# MCU.net
KiCad netlist of a schematic drawn in Altium Designer
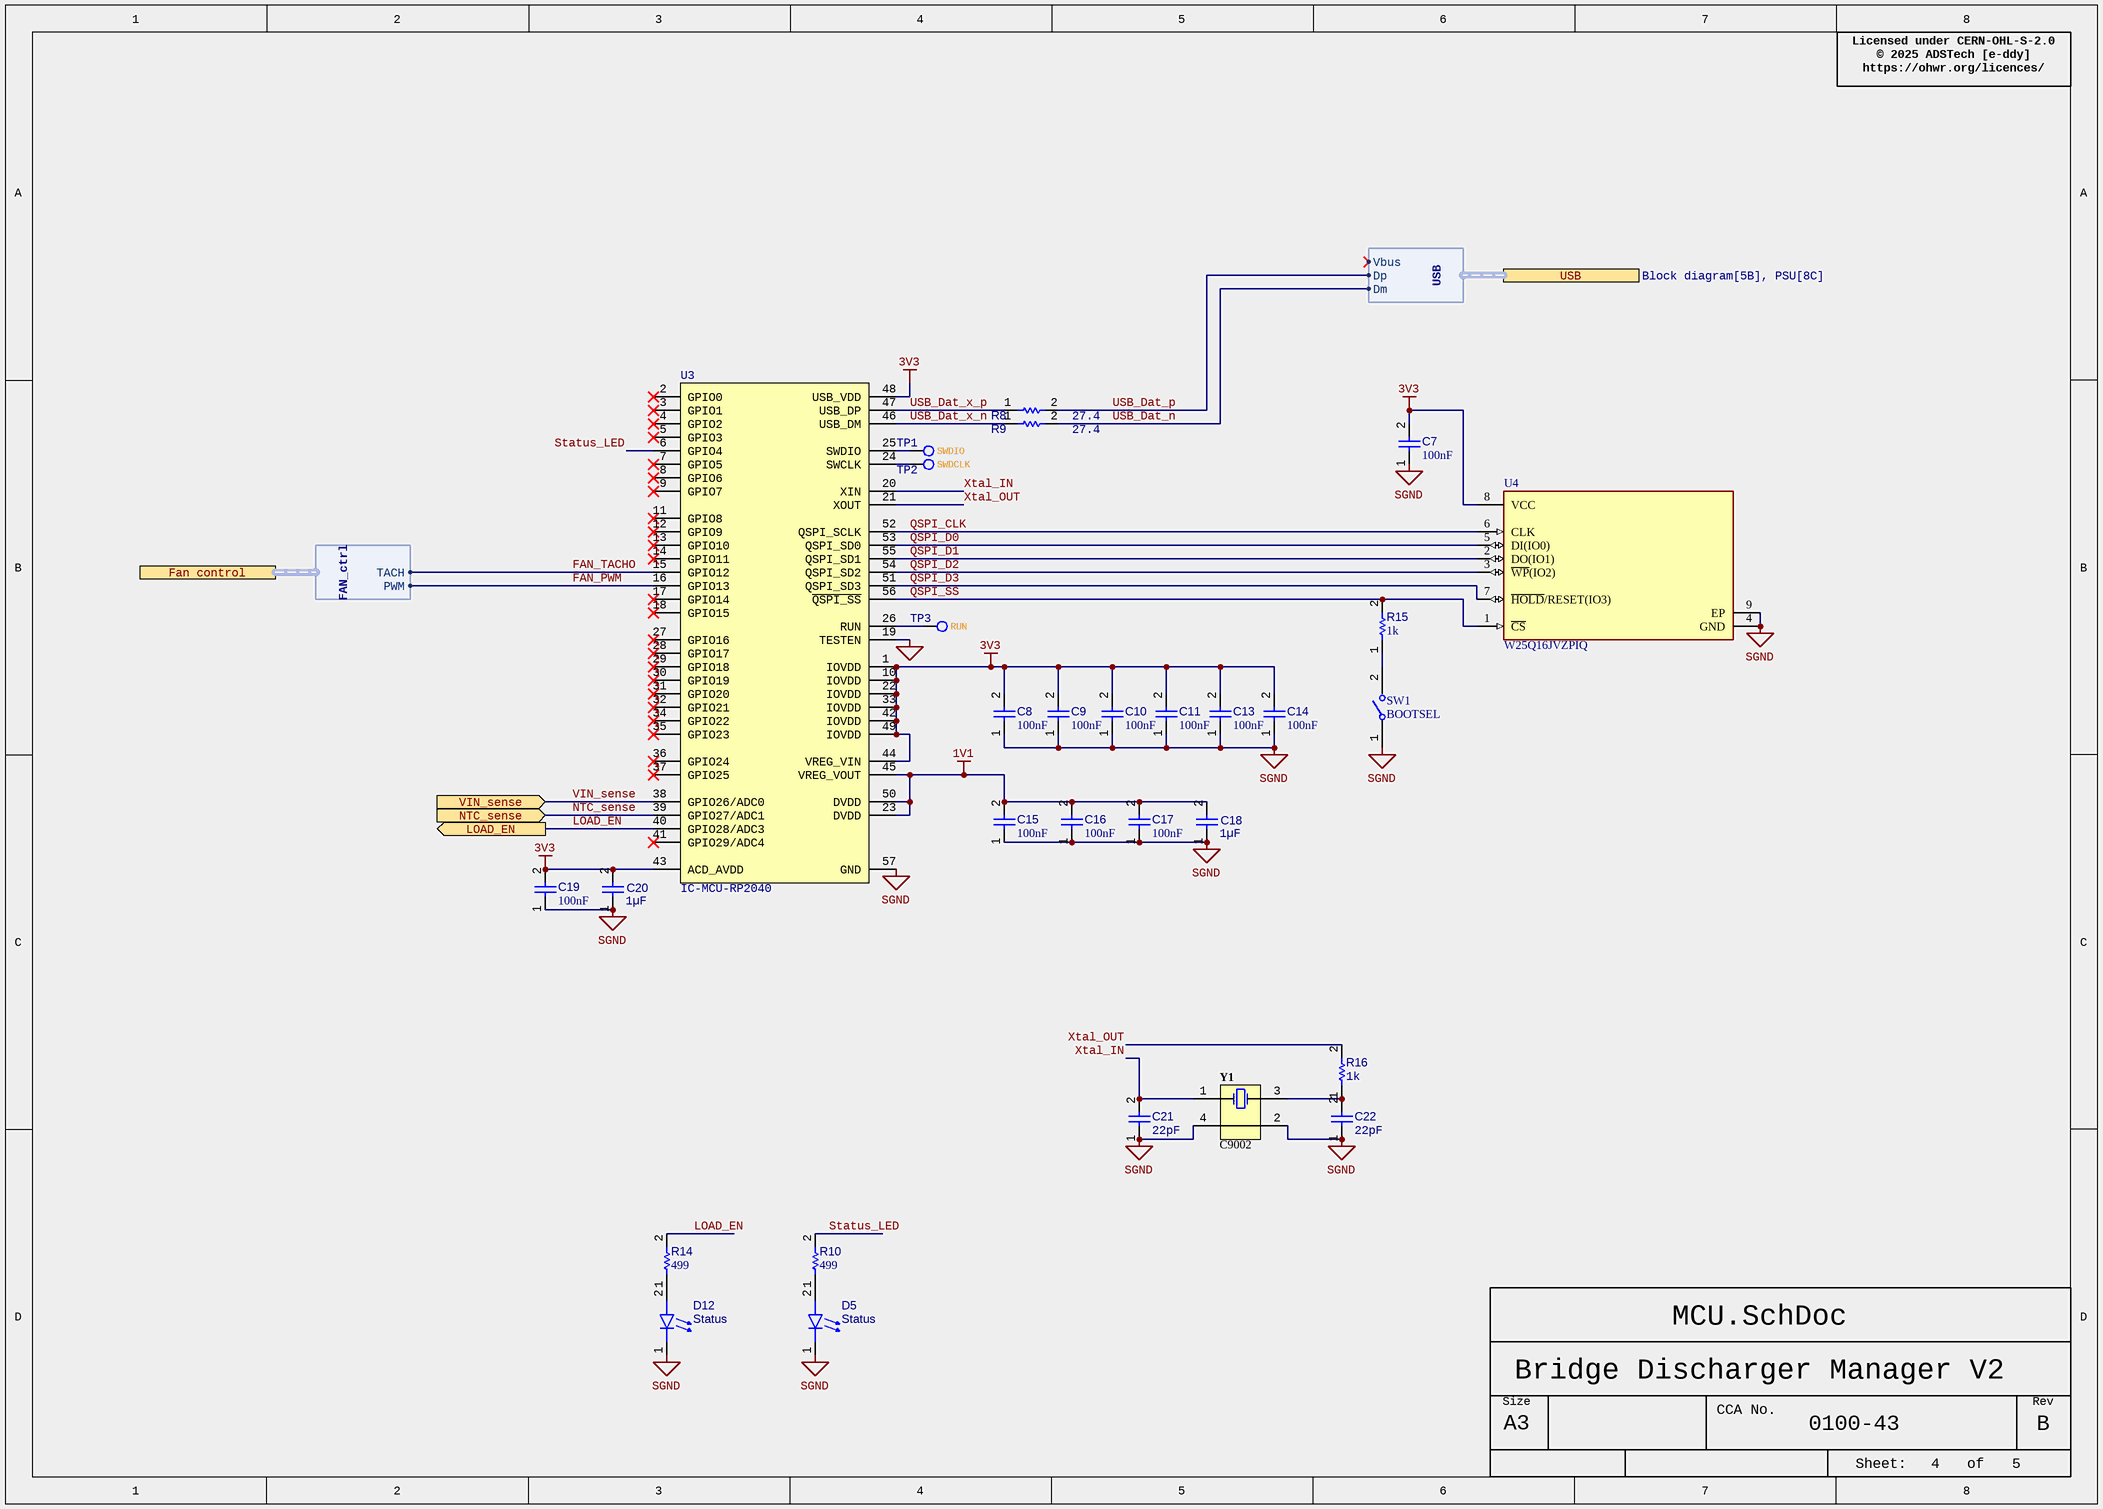
[diagram p0: MCU.SchDoc]

(export (version "E")
  (design (tool "Eeschema 10.0.6"))
  (components
    (comp (ref "C7")
      (value "100nF")
      (footprint "CAP_0402-IPC_B")
      (description "Multilayer Ceramic Capacitor, 0.1 uF, 50 V, ± 10%, X7R, 0402 [1005 Metric]")
      (fields (field (name "TOLERANCE") "10%") (field (name "Comment") "C-0402-CER-X7R-100nF-10%-50V"))
      (libsource (lib "FIME Lille") (part "CAP-NP-2"))
    )
    (comp (ref "C8")
      (value "100nF")
      (footprint "CAP_0402-IPC_B")
      (description "Multilayer Ceramic Capacitor, 0.1 uF, 50 V, ± 10%, X7R, 0402 [1005 Metric]")
      (fields (field (name "TOLERANCE") "10%") (field (name "Comment") "C-0402-CER-X7R-100nF-10%-50V"))
      (libsource (lib "FIME Lille") (part "CAP-NP-2"))
    )
    (comp (ref "C9")
      (value "100nF")
      (footprint "CAP_0402-IPC_B")
      (description "Multilayer Ceramic Capacitor, 0.1 uF, 50 V, ± 10%, X7R, 0402 [1005 Metric]")
      (fields (field (name "TOLERANCE") "10%") (field (name "Comment") "C-0402-CER-X7R-100nF-10%-50V"))
      (libsource (lib "FIME Lille") (part "CAP-NP-2"))
    )
    (comp (ref "C10")
      (value "100nF")
      (footprint "CAP_0402-IPC_B")
      (description "Multilayer Ceramic Capacitor, 0.1 uF, 50 V, ± 10%, X7R, 0402 [1005 Metric]")
      (fields (field (name "TOLERANCE") "10%") (field (name "Comment") "C-0402-CER-X7R-100nF-10%-50V"))
      (libsource (lib "FIME Lille") (part "CAP-NP-2"))
    )
    (comp (ref "C11")
      (value "100nF")
      (footprint "CAP_0402-IPC_B")
      (description "Multilayer Ceramic Capacitor, 0.1 uF, 50 V, ± 10%, X7R, 0402 [1005 Metric]")
      (fields (field (name "TOLERANCE") "10%") (field (name "Comment") "C-0402-CER-X7R-100nF-10%-50V"))
      (libsource (lib "FIME Lille") (part "CAP-NP-2"))
    )
    (comp (ref "C13")
      (value "100nF")
      (footprint "CAP_0402-IPC_B")
      (description "Multilayer Ceramic Capacitor, 0.1 uF, 50 V, ± 10%, X7R, 0402 [1005 Metric]")
      (fields (field (name "TOLERANCE") "10%") (field (name "Comment") "C-0402-CER-X7R-100nF-10%-50V"))
      (libsource (lib "FIME Lille") (part "CAP-NP-2"))
    )
    (comp (ref "C14")
      (value "100nF")
      (footprint "CAP_0402-IPC_B")
      (description "Multilayer Ceramic Capacitor, 0.1 uF, 50 V, ± 10%, X7R, 0402 [1005 Metric]")
      (fields (field (name "TOLERANCE") "10%") (field (name "Comment") "C-0402-CER-X7R-100nF-10%-50V"))
      (libsource (lib "FIME Lille") (part "CAP-NP-2"))
    )
    (comp (ref "C15")
      (value "100nF")
      (footprint "CAP_0402-IPC_B")
      (description "Multilayer Ceramic Capacitor, 0.1 uF, 50 V, ± 10%, X7R, 0402 [1005 Metric]")
      (fields (field (name "TOLERANCE") "10%") (field (name "Comment") "C-0402-CER-X7R-100nF-10%-50V"))
      (libsource (lib "FIME Lille") (part "CAP-NP-2"))
    )
    (comp (ref "C16")
      (value "100nF")
      (footprint "CAP_0402-IPC_B")
      (description "Multilayer Ceramic Capacitor, 0.1 uF, 50 V, ± 10%, X7R, 0402 [1005 Metric]")
      (fields (field (name "TOLERANCE") "10%") (field (name "Comment") "C-0402-CER-X7R-100nF-10%-50V"))
      (libsource (lib "FIME Lille") (part "CAP-NP-2"))
    )
    (comp (ref "C17")
      (value "100nF")
      (footprint "CAP_0402-IPC_B")
      (description "Multilayer Ceramic Capacitor, 0.1 uF, 50 V, ± 10%, X7R, 0402 [1005 Metric]")
      (fields (field (name "TOLERANCE") "10%") (field (name "Comment") "C-0402-CER-X7R-100nF-10%-50V"))
      (libsource (lib "FIME Lille") (part "CAP-NP-2"))
    )
    (comp (ref "C18")
      (value "1µF")
      (footprint "CAP_0402-IPC_B")
      (fields (field (name "Comment") "C-0402-CER-X5R-1µF-10%-25V"))
      (libsource (lib "FIME Lille") (part "CAP-NP-2"))
    )
    (comp (ref "C19")
      (value "100nF")
      (footprint "CAP_0402-IPC_B")
      (description "Multilayer Ceramic Capacitor, 0.1 uF, 50 V, ± 10%, X7R, 0402 [1005 Metric]")
      (fields (field (name "TOLERANCE") "10%") (field (name "Comment") "C-0402-CER-X7R-100nF-10%-50V"))
      (libsource (lib "FIME Lille") (part "CAP-NP-2"))
    )
    (comp (ref "C20")
      (value "1µF")
      (footprint "CAP_0402-IPC_B")
      (fields (field (name "Comment") "C-0402-CER-X5R-1µF-10%-25V"))
      (libsource (lib "FIME Lille") (part "CAP-NP-2"))
    )
    (comp (ref "C21")
      (value "22pF")
      (footprint "CAP_0402-IPC_B")
      (description "Multilayer Ceramic Capacitors MLCC - SMD/SMT 50V 22pF C0G 0402 +/-1%")
      (fields (field (name "TOLERANCE") "1%") (field (name "Comment") "C-0402-C0G-22pF-50V-1%"))
      (libsource (lib "FIME Lille") (part "CAP-NP-2"))
    )
    (comp (ref "C22")
      (value "22pF")
      (footprint "CAP_0402-IPC_B")
      (description "Multilayer Ceramic Capacitors MLCC - SMD/SMT 50V 22pF C0G 0402 +/-1%")
      (fields (field (name "TOLERANCE") "1%") (field (name "Comment") "C-0402-C0G-22pF-50V-1%"))
      (libsource (lib "FIME Lille") (part "CAP-NP-2"))
    )
    (comp (ref "D5")
      (value "Status")
      (footprint "DIAL-0603-2_V")
      (description "Red 633nm 0603 LED")
      (libsource (lib "FIME Lille") (part "DIODE-LED-2"))
    )
    (comp (ref "D12")
      (value "Status")
      (footprint "DIAL-0603-2_V")
      (description "Red 633nm 0603 LED")
      (libsource (lib "FIME Lille") (part "DIODE-LED-2"))
    )
    (comp (ref "R8")
      (value "27.4")
      (footprint "RES-0402-IPC_B")
      (description "0402 27.4 Ω 1% 100ppm 0.063W Resistor")
      (fields (field (name "MPN") "CRCW040227R4FKED") (field (name "TOLERANCE") "1%"))
      (libsource (lib "FIME Lille") (part "RES-2"))
    )
    (comp (ref "R9")
      (value "27.4")
      (footprint "RES-0402-IPC_B")
      (description "0402 27.4 Ω 1% 100ppm 0.063W Resistor")
      (fields (field (name "MPN") "CRCW040227R4FKED") (field (name "TOLERANCE") "1%"))
      (libsource (lib "FIME Lille") (part "RES-2"))
    )
    (comp (ref "R10")
      (value "499")
      (footprint "RES-0402-IPC_B")
      (description "0402 499.0 Ω 1% 100ppm 0.063W Resistor")
      (fields (field (name "TOLERANCE") "1%") (field (name "MPN") "CRCW0402499RFKED"))
      (libsource (lib "FIME Lille") (part "RES-2"))
    )
    (comp (ref "R14")
      (value "499")
      (footprint "RES-0402-IPC_B")
      (description "0402 499.0 Ω 1% 100ppm 0.063W Resistor")
      (fields (field (name "TOLERANCE") "1%") (field (name "MPN") "CRCW0402499RFKED"))
      (libsource (lib "FIME Lille") (part "RES-2"))
    )
    (comp (ref "R15")
      (value "1k")
      (footprint "RES-0402-IPC_B")
      (description "0402 1000.0 Ω 1% 100ppm 0.063W Resistor")
      (fields (field (name "TOLERANCE") "1%") (field (name "MPN") "CRCW04021K00FKED"))
      (libsource (lib "FIME Lille") (part "RES-2"))
    )
    (comp (ref "R16")
      (value "1k")
      (footprint "RES-0402-IPC_B")
      (description "0402 1000.0 Ω 1% 100ppm 0.063W Resistor")
      (fields (field (name "MPN") "CRCW04021K00FKED") (field (name "POWER") "63mW"))
      (libsource (lib "FIME Lille") (part "RES-2"))
    )
    (comp (ref "SW1")
      (value "BOOTSEL")
      (footprint "FP-B3U-1000P-MFG")
      (libsource (lib "FIME Lille") (part "ae622034201233ca1abcedc05908f33"))
    )
    (comp (ref "TP1")
      (value "TP-DIRECT-1.2mm")
      (footprint "1.2mm test point - direct connect")
      (description "1.2mm standard round test point with direct connect")
      (fields (field (name "NAME") "SWDIO"))
      (libsource (lib "FIME Lille") (part "Test point"))
    )
    (comp (ref "TP2")
      (value "TP-DIRECT-1.2mm")
      (footprint "1.2mm test point - direct connect")
      (description "1.2mm standard round test point with direct connect")
      (fields (field (name "NAME") "SWDCLK"))
      (libsource (lib "FIME Lille") (part "Test point"))
    )
    (comp (ref "TP3")
      (value "TP-DIRECT-1.2mm")
      (footprint "1.2mm test point - direct connect")
      (description "1.2mm standard round test point with direct connect")
      (fields (field (name "NAME") "RUN"))
      (libsource (lib "FIME Lille") (part "Test point"))
    )
    (comp (ref "U3")
      (value "IC-MCU-RP2040")
      (footprint "QFN40P700X700X90_HS-57N")
      (description "264KB 30 133MHZ LQFN-56(7X7) Microcontrollers (mcu/mpu/soc) Rohs")
      (libsource (lib "FIME Lille") (part "IC-MCU-RP2040-Symbol-1"))
    )
    (comp (ref "U4")
      (value "W25Q16JVZPIQ")
      (footprint "FP-ZP-IPC_B")
      (description "IC FLASH 16MBIT SPI/QUAD 8WSON")
      (libsource (lib "Altium Content Vault") (part "4cb77c13ae9adfb05a25f85e82aeb43"))
    )
    (comp (ref "Y1")
      (value "C9002")
      (footprint "FP-ABM8-MFG")
      (description "Crystal 12MHz ±20ppm (Tol) ±50ppm (Stability) 18pF FUND 120Ohm 4-Pin Ultra Mini-CSMD T/R")
      (fields (field (name "TOLERANCE") "20ppm"))
      (libsource (lib "FIME Lille") (part "Copy of XTAL-2"))
    )
  )
  (nets
    (net (code "3") (name "/FAN_PWM") (class "Default")
      (node (ref "U3") (pin "16") (pinfunction "GPIO13_16") (pintype "passive"))
    )
    (net (code "4") (name "/FAN_TACHO") (class "Default")
      (node (ref "U3") (pin "15") (pinfunction "GPIO12_15") (pintype "passive"))
    )
    (net (code "5") (name "/LOAD_EN") (class "Default")
      (node (ref "R14") (pin "2") (pinfunction "2_2") (pintype "passive"))
      (node (ref "U3") (pin "40") (pinfunction "GPIO28/ADC3_40") (pintype "passive"))
    )
    (net (code "6") (name "/NTC_sense") (class "Default")
      (node (ref "U3") (pin "39") (pinfunction "GPIO27/ADC1_39") (pintype "passive"))
    )
    (net (code "7") (name "/QSPI_CLK") (class "Default")
      (node (ref "U3") (pin "52") (pinfunction "QSPI_SCLK_52") (pintype "passive"))
      (node (ref "U4") (pin "6") (pinfunction "CLK_6") (pintype "input"))
    )
    (net (code "8") (name "/QSPI_D0") (class "Default")
      (node (ref "U3") (pin "53") (pinfunction "QSPI_SD0_53") (pintype "passive"))
      (node (ref "U4") (pin "5") (pinfunction "DI(IO0)_5") (pintype "bidirectional"))
    )
    (net (code "9") (name "/QSPI_D1") (class "Default")
      (node (ref "U3") (pin "55") (pinfunction "QSPI_SD1_55") (pintype "passive"))
      (node (ref "U4") (pin "2") (pinfunction "DO(IO1)_2") (pintype "bidirectional"))
    )
    (net (code "10") (name "/QSPI_D2") (class "Default")
      (node (ref "U3") (pin "54") (pinfunction "QSPI_SD2_54") (pintype "passive"))
      (node (ref "U4") (pin "3") (pinfunction "~{WP}(IO2)_3") (pintype "bidirectional"))
    )
    (net (code "11") (name "/QSPI_D3") (class "Default")
      (node (ref "U3") (pin "51") (pinfunction "QSPI_SD3_51") (pintype "passive"))
      (node (ref "U4") (pin "7") (pinfunction "~{HOLD}/RESET(IO3)_7") (pintype "bidirectional"))
    )
    (net (code "12") (name "/QSPI_SS") (class "Default")
      (node (ref "R15") (pin "2") (pinfunction "2_2") (pintype "passive"))
      (node (ref "U3") (pin "56") (pinfunction "QSPI_SS_56") (pintype "passive"))
      (node (ref "U4") (pin "1") (pinfunction "~{CS}_1") (pintype "input"))
    )
    (net (code "13") (name "/Status_LED") (class "Default")
      (node (ref "R10") (pin "2") (pinfunction "2_2") (pintype "passive"))
      (node (ref "U3") (pin "6") (pinfunction "GPIO4_6") (pintype "passive"))
    )
    (net (code "14") (name "/USB_Dat_n") (class "Default")
      (node (ref "R9") (pin "2") (pinfunction "2_2") (pintype "passive"))
    )
    (net (code "15") (name "/USB_Dat_p") (class "Default")
      (node (ref "R8") (pin "2") (pinfunction "2_2") (pintype "passive"))
    )
    (net (code "16") (name "/USB_Dat_x_n") (class "Default")
      (node (ref "R9") (pin "1") (pinfunction "1_1") (pintype "passive"))
      (node (ref "U3") (pin "46") (pinfunction "USB_DM_46") (pintype "passive"))
    )
    (net (code "17") (name "/USB_Dat_x_p") (class "Default")
      (node (ref "R8") (pin "1") (pinfunction "1_1") (pintype "passive"))
      (node (ref "U3") (pin "47") (pinfunction "USB_DP_47") (pintype "passive"))
    )
    (net (code "18") (name "/VIN_sense") (class "Default")
      (node (ref "U3") (pin "38") (pinfunction "GPIO26/ADC0_38") (pintype "passive"))
    )
    (net (code "19") (name "/Xtal_IN") (class "Default")
      (node (ref "C21") (pin "2") (pinfunction "2_2") (pintype "passive"))
      (node (ref "U3") (pin "20") (pinfunction "XIN_20") (pintype "passive"))
      (node (ref "Y1") (pin "1") (pinfunction "1_1") (pintype "passive"))
    )
    (net (code "20") (name "/Xtal_OUT") (class "Default")
      (node (ref "R16") (pin "2") (pinfunction "2_2") (pintype "passive"))
      (node (ref "U3") (pin "21") (pinfunction "XOUT_21") (pintype "passive"))
    )
    (net (code "23") (name "1V1") (class "Default")
      (node (ref "C15") (pin "2") (pinfunction "2_2") (pintype "passive"))
      (node (ref "C16") (pin "2") (pinfunction "2_2") (pintype "passive"))
      (node (ref "C17") (pin "2") (pinfunction "2_2") (pintype "passive"))
      (node (ref "C18") (pin "2") (pinfunction "2_2") (pintype "passive"))
      (node (ref "U3") (pin "23") (pinfunction "DVDD_23") (pintype "passive"))
      (node (ref "U3") (pin "45") (pinfunction "VREG_VOUT_45") (pintype "passive"))
      (node (ref "U3") (pin "50") (pinfunction "DVDD_50") (pintype "passive"))
    )
    (net (code "24") (name "3V3") (class "Default")
      (node (ref "C10") (pin "2") (pinfunction "2_2") (pintype "passive"))
      (node (ref "C11") (pin "2") (pinfunction "2_2") (pintype "passive"))
      (node (ref "C13") (pin "2") (pinfunction "2_2") (pintype "passive"))
      (node (ref "C14") (pin "2") (pinfunction "2_2") (pintype "passive"))
      (node (ref "C19") (pin "2") (pinfunction "2_2") (pintype "passive"))
      (node (ref "C20") (pin "2") (pinfunction "2_2") (pintype "passive"))
      (node (ref "C7") (pin "2") (pinfunction "2_2") (pintype "passive"))
      (node (ref "C8") (pin "2") (pinfunction "2_2") (pintype "passive"))
      (node (ref "C9") (pin "2") (pinfunction "2_2") (pintype "passive"))
      (node (ref "U3") (pin "1") (pinfunction "IOVDD_1") (pintype "passive"))
      (node (ref "U3") (pin "10") (pinfunction "IOVDD_10") (pintype "passive"))
      (node (ref "U3") (pin "22") (pinfunction "IOVDD_22") (pintype "passive"))
      (node (ref "U3") (pin "33") (pinfunction "IOVDD_33") (pintype "passive"))
      (node (ref "U3") (pin "42") (pinfunction "IOVDD_42") (pintype "passive"))
      (node (ref "U3") (pin "43") (pinfunction "ACD_AVDD_43") (pintype "passive"))
      (node (ref "U3") (pin "44") (pinfunction "VREG_VIN_44") (pintype "passive"))
      (node (ref "U3") (pin "48") (pinfunction "USB_VDD_48") (pintype "passive"))
      (node (ref "U3") (pin "49") (pinfunction "IOVDD_49") (pintype "passive"))
      (node (ref "U4") (pin "8") (pinfunction "VCC_8") (pintype "power_in"))
    )
    (net (code "25") (name "Net-(C22-Pad2)") (class "Default")
      (node (ref "C22") (pin "2") (pinfunction "2_2") (pintype "passive"))
      (node (ref "R16") (pin "1") (pinfunction "1_1") (pintype "passive"))
      (node (ref "Y1") (pin "3") (pinfunction "3_3") (pintype "passive"))
    )
    (net (code "26") (name "Net-(D5-A)") (class "Default")
      (node (ref "D5") (pin "2") (pinfunction "A_2") (pintype "passive"))
      (node (ref "R10") (pin "1") (pinfunction "1_1") (pintype "passive"))
    )
    (net (code "27") (name "Net-(D12-A)") (class "Default")
      (node (ref "D12") (pin "2") (pinfunction "A_2") (pintype "passive"))
      (node (ref "R14") (pin "1") (pinfunction "1_1") (pintype "passive"))
    )
    (net (code "28") (name "Net-(R15-Pad1)") (class "Default")
      (node (ref "R15") (pin "1") (pinfunction "1_1") (pintype "passive"))
      (node (ref "SW1") (pin "2") (pinfunction "2_2") (pintype "passive"))
    )
    (net (code "29") (name "Net-(U3-RUN)") (class "Default")
      (node (ref "TP3") (pin "1") (pinfunction "1_1") (pintype "passive"))
      (node (ref "U3") (pin "26") (pinfunction "RUN_26") (pintype "passive"))
    )
    (net (code "30") (name "Net-(U3-SWCLK)") (class "Default")
      (node (ref "TP2") (pin "1") (pinfunction "1_1") (pintype "passive"))
      (node (ref "U3") (pin "24") (pinfunction "SWCLK_24") (pintype "passive"))
    )
    (net (code "31") (name "Net-(U3-SWDIO)") (class "Default")
      (node (ref "TP1") (pin "1") (pinfunction "1_1") (pintype "passive"))
      (node (ref "U3") (pin "25") (pinfunction "SWDIO_25") (pintype "passive"))
    )
    (net (code "32") (name "SGND") (class "Default")
      (node (ref "C10") (pin "1") (pinfunction "1_1") (pintype "passive"))
      (node (ref "C11") (pin "1") (pinfunction "1_1") (pintype "passive"))
      (node (ref "C13") (pin "1") (pinfunction "1_1") (pintype "passive"))
      (node (ref "C14") (pin "1") (pinfunction "1_1") (pintype "passive"))
      (node (ref "C15") (pin "1") (pinfunction "1_1") (pintype "passive"))
      (node (ref "C16") (pin "1") (pinfunction "1_1") (pintype "passive"))
      (node (ref "C17") (pin "1") (pinfunction "1_1") (pintype "passive"))
      (node (ref "C18") (pin "1") (pinfunction "1_1") (pintype "passive"))
      (node (ref "C19") (pin "1") (pinfunction "1_1") (pintype "passive"))
      (node (ref "C20") (pin "1") (pinfunction "1_1") (pintype "passive"))
      (node (ref "C21") (pin "1") (pinfunction "1_1") (pintype "passive"))
      (node (ref "C22") (pin "1") (pinfunction "1_1") (pintype "passive"))
      (node (ref "C7") (pin "1") (pinfunction "1_1") (pintype "passive"))
      (node (ref "C8") (pin "1") (pinfunction "1_1") (pintype "passive"))
      (node (ref "C9") (pin "1") (pinfunction "1_1") (pintype "passive"))
      (node (ref "D12") (pin "1") (pinfunction "K_1") (pintype "passive"))
      (node (ref "D5") (pin "1") (pinfunction "K_1") (pintype "passive"))
      (node (ref "SW1") (pin "1") (pinfunction "1_1") (pintype "passive"))
      (node (ref "U3") (pin "19") (pinfunction "TESTEN_19") (pintype "passive"))
      (node (ref "U3") (pin "57") (pinfunction "GND_57") (pintype "passive"))
      (node (ref "U4") (pin "4") (pinfunction "GND_4") (pintype "power_in"))
      (node (ref "U4") (pin "9") (pinfunction "EP_9") (pintype "passive"))
      (node (ref "Y1") (pin "2") (pinfunction "2_2") (pintype "passive"))
      (node (ref "Y1") (pin "4") (pinfunction "4_4") (pintype "passive"))
    )
    (net (code "33") (name "unconnected-(U3-GPIO0-Pad2)") (class "Default")
      (node (ref "U3") (pin "2") (pinfunction "GPIO0_2") (pintype "passive+no_connect"))
    )
    (net (code "34") (name "unconnected-(U3-GPIO1-Pad3)") (class "Default")
      (node (ref "U3") (pin "3") (pinfunction "GPIO1_3") (pintype "passive+no_connect"))
    )
    (net (code "35") (name "unconnected-(U3-GPIO2-Pad4)") (class "Default")
      (node (ref "U3") (pin "4") (pinfunction "GPIO2_4") (pintype "passive+no_connect"))
    )
    (net (code "36") (name "unconnected-(U3-GPIO3-Pad5)") (class "Default")
      (node (ref "U3") (pin "5") (pinfunction "GPIO3_5") (pintype "passive+no_connect"))
    )
    (net (code "37") (name "unconnected-(U3-GPIO5-Pad7)") (class "Default")
      (node (ref "U3") (pin "7") (pinfunction "GPIO5_7") (pintype "passive+no_connect"))
    )
    (net (code "38") (name "unconnected-(U3-GPIO6-Pad8)") (class "Default")
      (node (ref "U3") (pin "8") (pinfunction "GPIO6_8") (pintype "passive+no_connect"))
    )
    (net (code "39") (name "unconnected-(U3-GPIO7-Pad9)") (class "Default")
      (node (ref "U3") (pin "9") (pinfunction "GPIO7_9") (pintype "passive+no_connect"))
    )
    (net (code "40") (name "unconnected-(U3-GPIO8-Pad11)") (class "Default")
      (node (ref "U3") (pin "11") (pinfunction "GPIO8_11") (pintype "passive+no_connect"))
    )
    (net (code "41") (name "unconnected-(U3-GPIO9-Pad12)") (class "Default")
      (node (ref "U3") (pin "12") (pinfunction "GPIO9_12") (pintype "passive+no_connect"))
    )
    (net (code "42") (name "unconnected-(U3-GPIO10-Pad13)") (class "Default")
      (node (ref "U3") (pin "13") (pinfunction "GPIO10_13") (pintype "passive+no_connect"))
    )
    (net (code "43") (name "unconnected-(U3-GPIO11-Pad14)") (class "Default")
      (node (ref "U3") (pin "14") (pinfunction "GPIO11_14") (pintype "passive+no_connect"))
    )
    (net (code "44") (name "unconnected-(U3-GPIO14-Pad17)") (class "Default")
      (node (ref "U3") (pin "17") (pinfunction "GPIO14_17") (pintype "passive+no_connect"))
    )
    (net (code "45") (name "unconnected-(U3-GPIO15-Pad18)") (class "Default")
      (node (ref "U3") (pin "18") (pinfunction "GPIO15_18") (pintype "passive+no_connect"))
    )
    (net (code "46") (name "unconnected-(U3-GPIO16-Pad27)") (class "Default")
      (node (ref "U3") (pin "27") (pinfunction "GPIO16_27") (pintype "passive+no_connect"))
    )
    (net (code "47") (name "unconnected-(U3-GPIO17-Pad28)") (class "Default")
      (node (ref "U3") (pin "28") (pinfunction "GPIO17_28") (pintype "passive+no_connect"))
    )
    (net (code "48") (name "unconnected-(U3-GPIO18-Pad29)") (class "Default")
      (node (ref "U3") (pin "29") (pinfunction "GPIO18_29") (pintype "passive+no_connect"))
    )
    (net (code "49") (name "unconnected-(U3-GPIO19-Pad30)") (class "Default")
      (node (ref "U3") (pin "30") (pinfunction "GPIO19_30") (pintype "passive+no_connect"))
    )
    (net (code "50") (name "unconnected-(U3-GPIO20-Pad31)") (class "Default")
      (node (ref "U3") (pin "31") (pinfunction "GPIO20_31") (pintype "passive+no_connect"))
    )
    (net (code "51") (name "unconnected-(U3-GPIO21-Pad32)") (class "Default")
      (node (ref "U3") (pin "32") (pinfunction "GPIO21_32") (pintype "passive+no_connect"))
    )
    (net (code "52") (name "unconnected-(U3-GPIO22-Pad34)") (class "Default")
      (node (ref "U3") (pin "34") (pinfunction "GPIO22_34") (pintype "passive+no_connect"))
    )
    (net (code "53") (name "unconnected-(U3-GPIO23-Pad35)") (class "Default")
      (node (ref "U3") (pin "35") (pinfunction "GPIO23_35") (pintype "passive+no_connect"))
    )
    (net (code "54") (name "unconnected-(U3-GPIO24-Pad36)") (class "Default")
      (node (ref "U3") (pin "36") (pinfunction "GPIO24_36") (pintype "passive+no_connect"))
    )
    (net (code "55") (name "unconnected-(U3-GPIO25-Pad37)") (class "Default")
      (node (ref "U3") (pin "37") (pinfunction "GPIO25_37") (pintype "passive+no_connect"))
    )
    (net (code "56") (name "unconnected-(U3-GPIO29{slash}ADC4-Pad41)") (class "Default")
      (node (ref "U3") (pin "41") (pinfunction "GPIO29/ADC4_41") (pintype "passive+no_connect"))
    )
  )
)
